# Sheet_1.net
KiCad netlist of a schematic drawn in EasyEDA
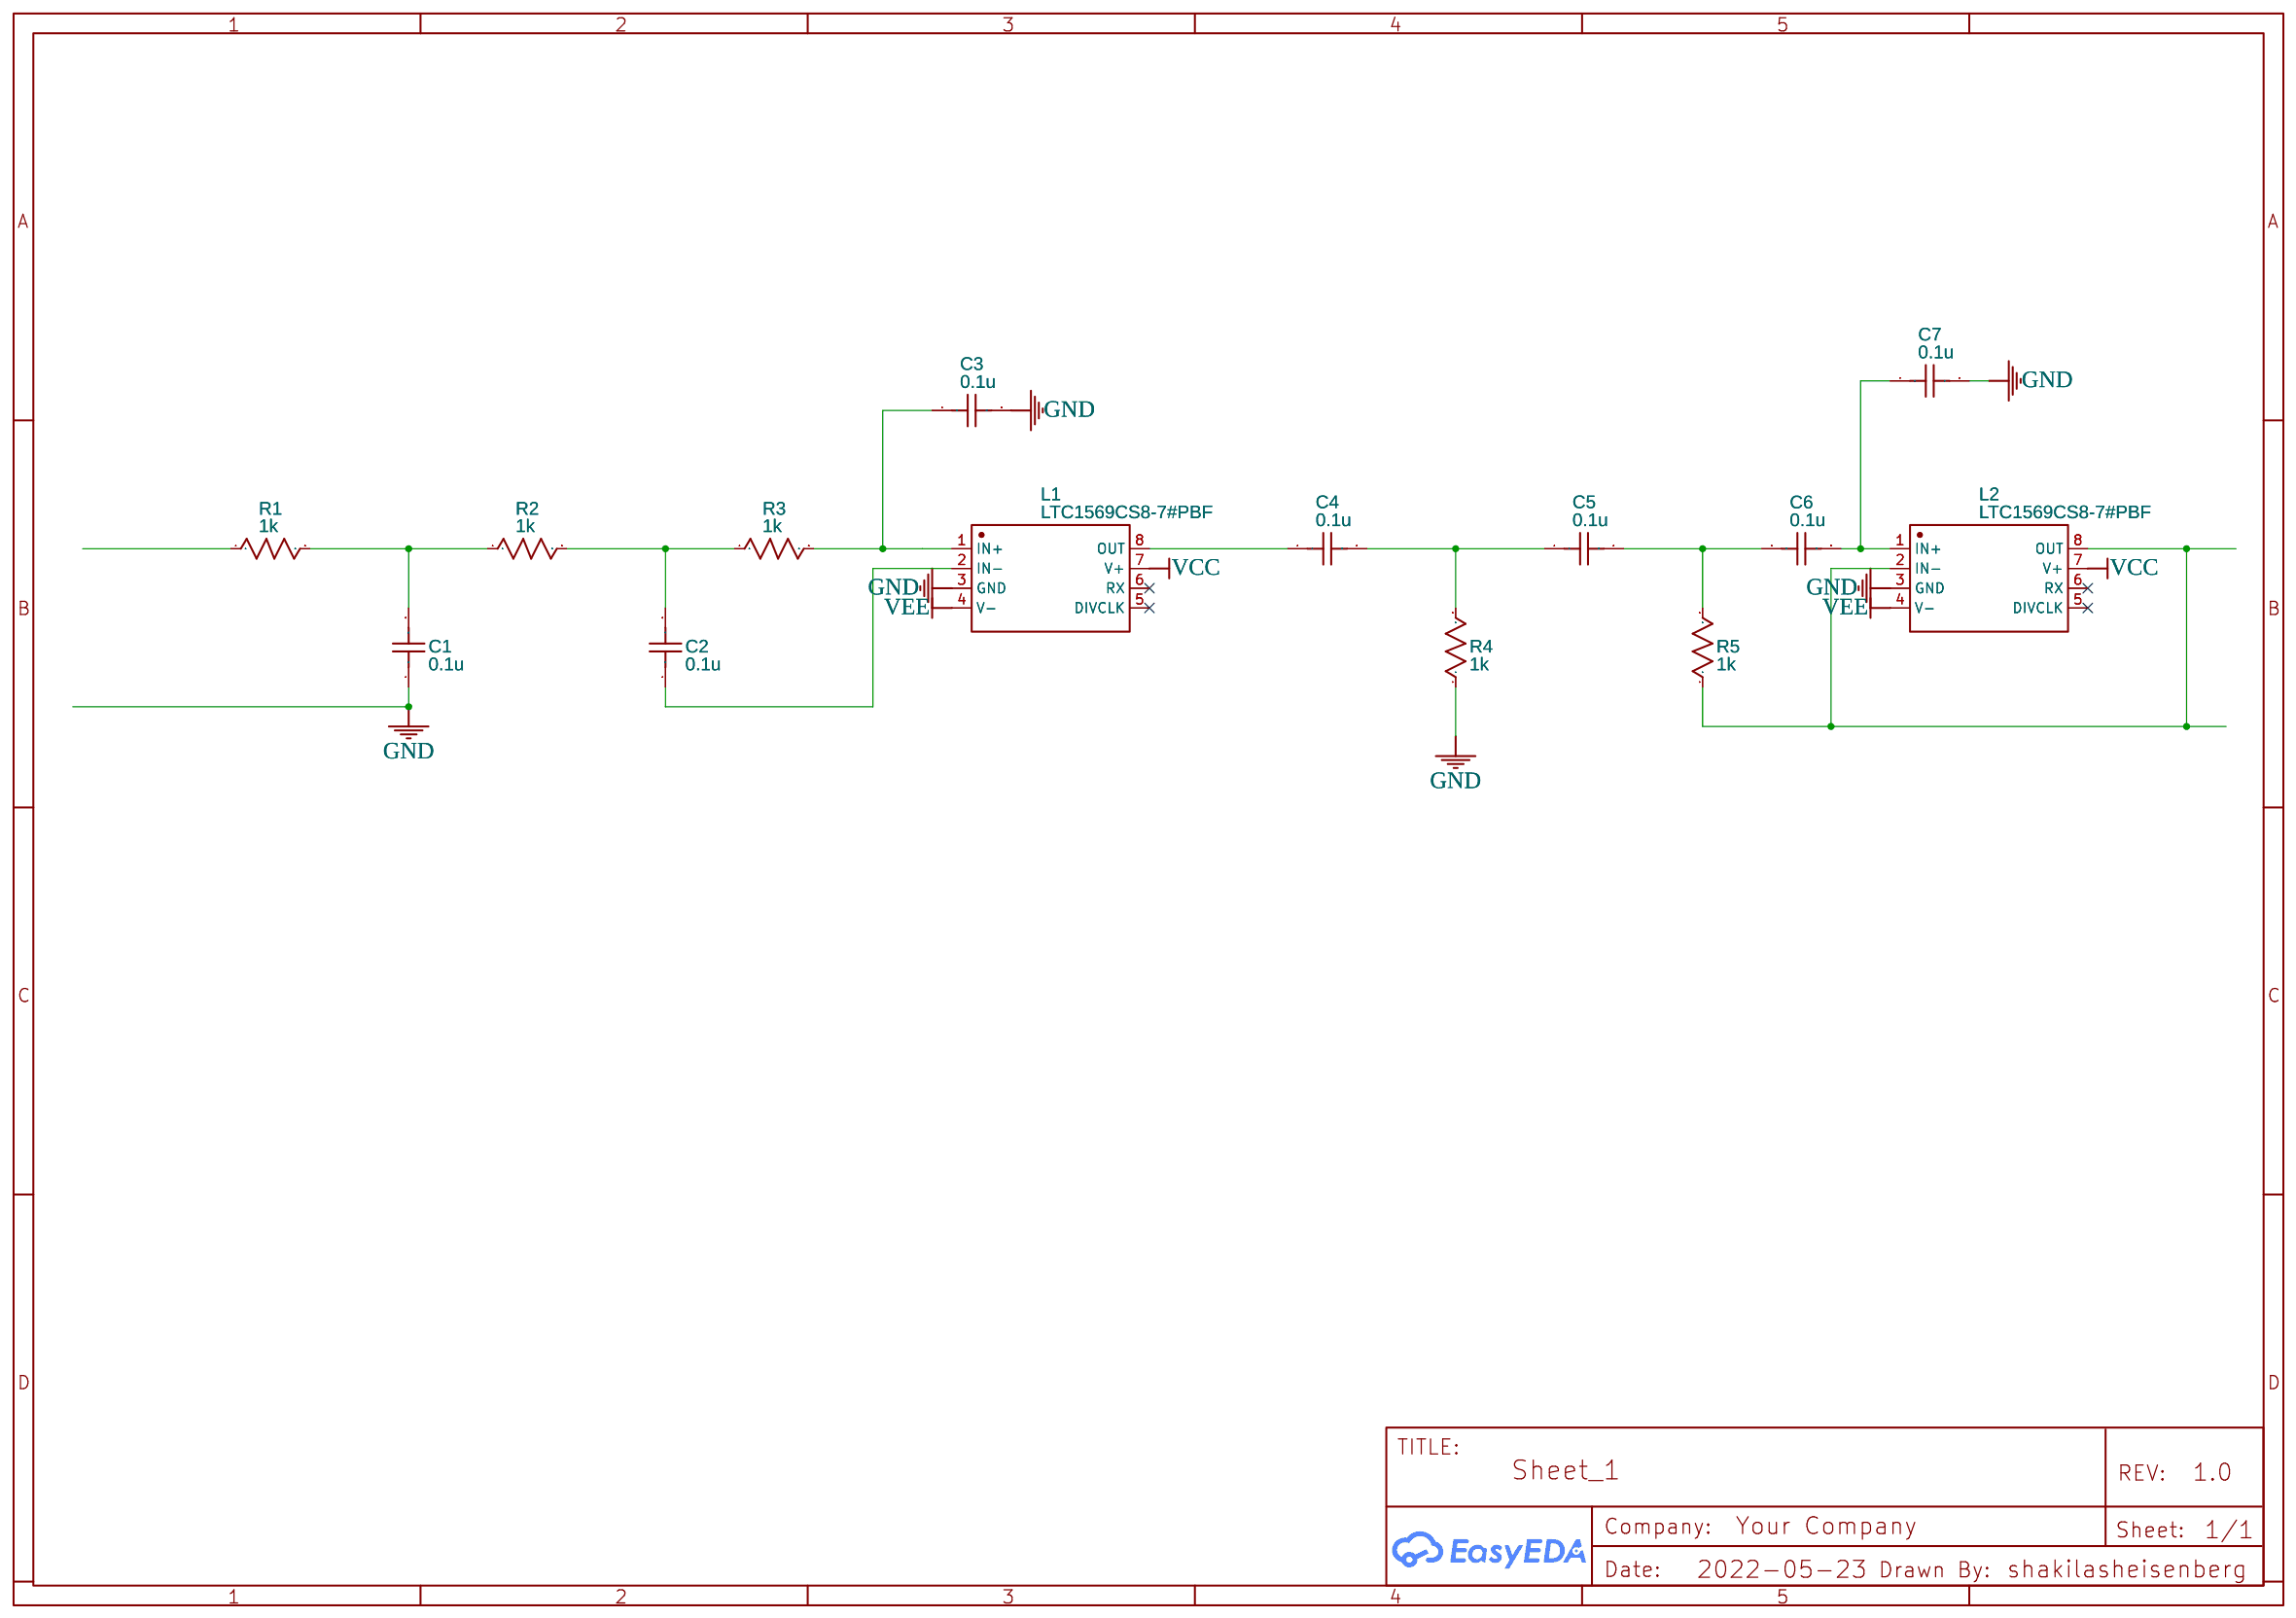
[diagram p0: schematic sheet]

(export (version "E")
  (design (tool "Eeschema 10.0.6"))
  (components
    (comp (ref "C1") (value "0.1u") (libsource (lib "") (part "C_0603_US_1")))
    (comp (ref "C2") (value "0.1u") (libsource (lib "") (part "C_0603_US_1")))
    (comp (ref "C3") (value "0.1u") (libsource (lib "") (part "C_0603_US")))
    (comp (ref "C4") (value "0.1u") (libsource (lib "") (part "C_0603_US")))
    (comp (ref "C5") (value "0.1u") (libsource (lib "") (part "C_0603_US")))
    (comp (ref "C6") (value "0.1u") (libsource (lib "") (part "C_0603_US")))
    (comp (ref "C7") (value "0.1u") (libsource (lib "") (part "C_0603_US")))
    (comp (ref "L1")
      (value "LTC1569CS8-7#PBF")
      (fields (field (name "BOM_Supplier Part") "C117415"))
      (libsource (lib "") (part "LTC1569CS8-7#PBF"))
    )
    (comp (ref "L2")
      (value "LTC1569CS8-7#PBF")
      (fields (field (name "BOM_Supplier Part") "C117415"))
      (libsource (lib "") (part "LTC1569CS8-7#PBF"))
    )
    (comp (ref "R1") (value "1k") (libsource (lib "") (part "R_0603_US_1")))
    (comp (ref "R2") (value "1k") (libsource (lib "") (part "R_0603_US_1")))
    (comp (ref "R3") (value "1k") (libsource (lib "") (part "R_0603_US_1")))
    (comp (ref "R4") (value "1k") (libsource (lib "") (part "R_0603_US")))
    (comp (ref "R5") (value "1k") (libsource (lib "") (part "R_0603_US")))
  )
  (nets
    (net (code "1") (name "GND") (class "Default")
      (node (ref "C1") (pin "1") (pinfunction "1_1") (pintype "unspecified"))
      (node (ref "C3") (pin "2") (pinfunction "2_2") (pintype "unspecified"))
      (node (ref "C7") (pin "2") (pinfunction "2_2") (pintype "unspecified"))
      (node (ref "L1") (pin "3") (pinfunction "GND_3") (pintype "unspecified"))
      (node (ref "L2") (pin "3") (pinfunction "GND_3") (pintype "unspecified"))
      (node (ref "R4") (pin "1") (pinfunction "1_1") (pintype "unspecified"))
    )
    (net (code "2") (name "Net-(C1-Pad2)") (class "Default")
      (node (ref "C1") (pin "2") (pinfunction "2_2") (pintype "unspecified"))
      (node (ref "R1") (pin "2") (pinfunction "2_2") (pintype "unspecified"))
      (node (ref "R2") (pin "1") (pinfunction "1_1") (pintype "unspecified"))
    )
    (net (code "3") (name "Net-(C2-Pad2)") (class "Default")
      (node (ref "C2") (pin "2") (pinfunction "2_2") (pintype "unspecified"))
      (node (ref "R2") (pin "2") (pinfunction "2_2") (pintype "unspecified"))
      (node (ref "R3") (pin "1") (pinfunction "1_1") (pintype "unspecified"))
    )
    (net (code "4") (name "Net-(C4-Pad2)") (class "Default")
      (node (ref "C4") (pin "2") (pinfunction "2_2") (pintype "unspecified"))
      (node (ref "C5") (pin "1") (pinfunction "1_1") (pintype "unspecified"))
      (node (ref "R4") (pin "2") (pinfunction "2_2") (pintype "unspecified"))
    )
    (net (code "5") (name "Net-(C5-Pad2)") (class "Default")
      (node (ref "C5") (pin "2") (pinfunction "2_2") (pintype "unspecified"))
      (node (ref "C6") (pin "1") (pinfunction "1_1") (pintype "unspecified"))
      (node (ref "R5") (pin "2") (pinfunction "2_2") (pintype "unspecified"))
    )
    (net (code "6") (name "Net-(L1-IN+)") (class "Default")
      (node (ref "C3") (pin "1") (pinfunction "1_1") (pintype "unspecified"))
      (node (ref "L1") (pin "1") (pinfunction "IN+_1") (pintype "unspecified"))
      (node (ref "R3") (pin "2") (pinfunction "2_2") (pintype "unspecified"))
    )
    (net (code "7") (name "Net-(L1-IN-)") (class "Default")
      (node (ref "C2") (pin "1") (pinfunction "1_1") (pintype "unspecified"))
      (node (ref "L1") (pin "2") (pinfunction "IN-_2") (pintype "unspecified"))
    )
    (net (code "8") (name "Net-(L1-OUT)") (class "Default")
      (node (ref "C4") (pin "1") (pinfunction "1_1") (pintype "unspecified"))
      (node (ref "L1") (pin "8") (pinfunction "OUT_8") (pintype "unspecified"))
    )
    (net (code "9") (name "Net-(L2-IN+)") (class "Default")
      (node (ref "C6") (pin "2") (pinfunction "2_2") (pintype "unspecified"))
      (node (ref "C7") (pin "1") (pinfunction "1_1") (pintype "unspecified"))
      (node (ref "L2") (pin "1") (pinfunction "IN+_1") (pintype "unspecified"))
    )
    (net (code "10") (name "Net-(L2-IN-)") (class "Default")
      (node (ref "L2") (pin "2") (pinfunction "IN-_2") (pintype "unspecified"))
      (node (ref "L2") (pin "8") (pinfunction "OUT_8") (pintype "unspecified"))
      (node (ref "R5") (pin "1") (pinfunction "1_1") (pintype "unspecified"))
    )
    (net (code "11") (name "VCC") (class "Default")
      (node (ref "L1") (pin "7") (pinfunction "V+_7") (pintype "unspecified"))
      (node (ref "L2") (pin "7") (pinfunction "V+_7") (pintype "unspecified"))
    )
    (net (code "12") (name "VEE") (class "Default")
      (node (ref "L1") (pin "4") (pinfunction "V-_4") (pintype "unspecified"))
      (node (ref "L2") (pin "4") (pinfunction "V-_4") (pintype "unspecified"))
    )
    (net (code "13") (name "unconnected-(L1-DIVCLK-Pad5)") (class "Default")
      (node (ref "L1") (pin "5") (pinfunction "DIVCLK_5") (pintype "unspecified+no_connect"))
    )
    (net (code "14") (name "unconnected-(L1-RX-Pad6)") (class "Default")
      (node (ref "L1") (pin "6") (pinfunction "RX_6") (pintype "unspecified+no_connect"))
    )
    (net (code "15") (name "unconnected-(L2-DIVCLK-Pad5)") (class "Default")
      (node (ref "L2") (pin "5") (pinfunction "DIVCLK_5") (pintype "unspecified+no_connect"))
    )
    (net (code "16") (name "unconnected-(L2-RX-Pad6)") (class "Default")
      (node (ref "L2") (pin "6") (pinfunction "RX_6") (pintype "unspecified+no_connect"))
    )
    (net (code "17") (name "unconnected-(R1-Pad1)") (class "Default")
      (node (ref "R1") (pin "1") (pinfunction "1_1") (pintype "unspecified"))
    )
  )
)
